# USB_Type-C_Port_V2_0.net
KiCad netlist of a schematic drawn in Altium Designer
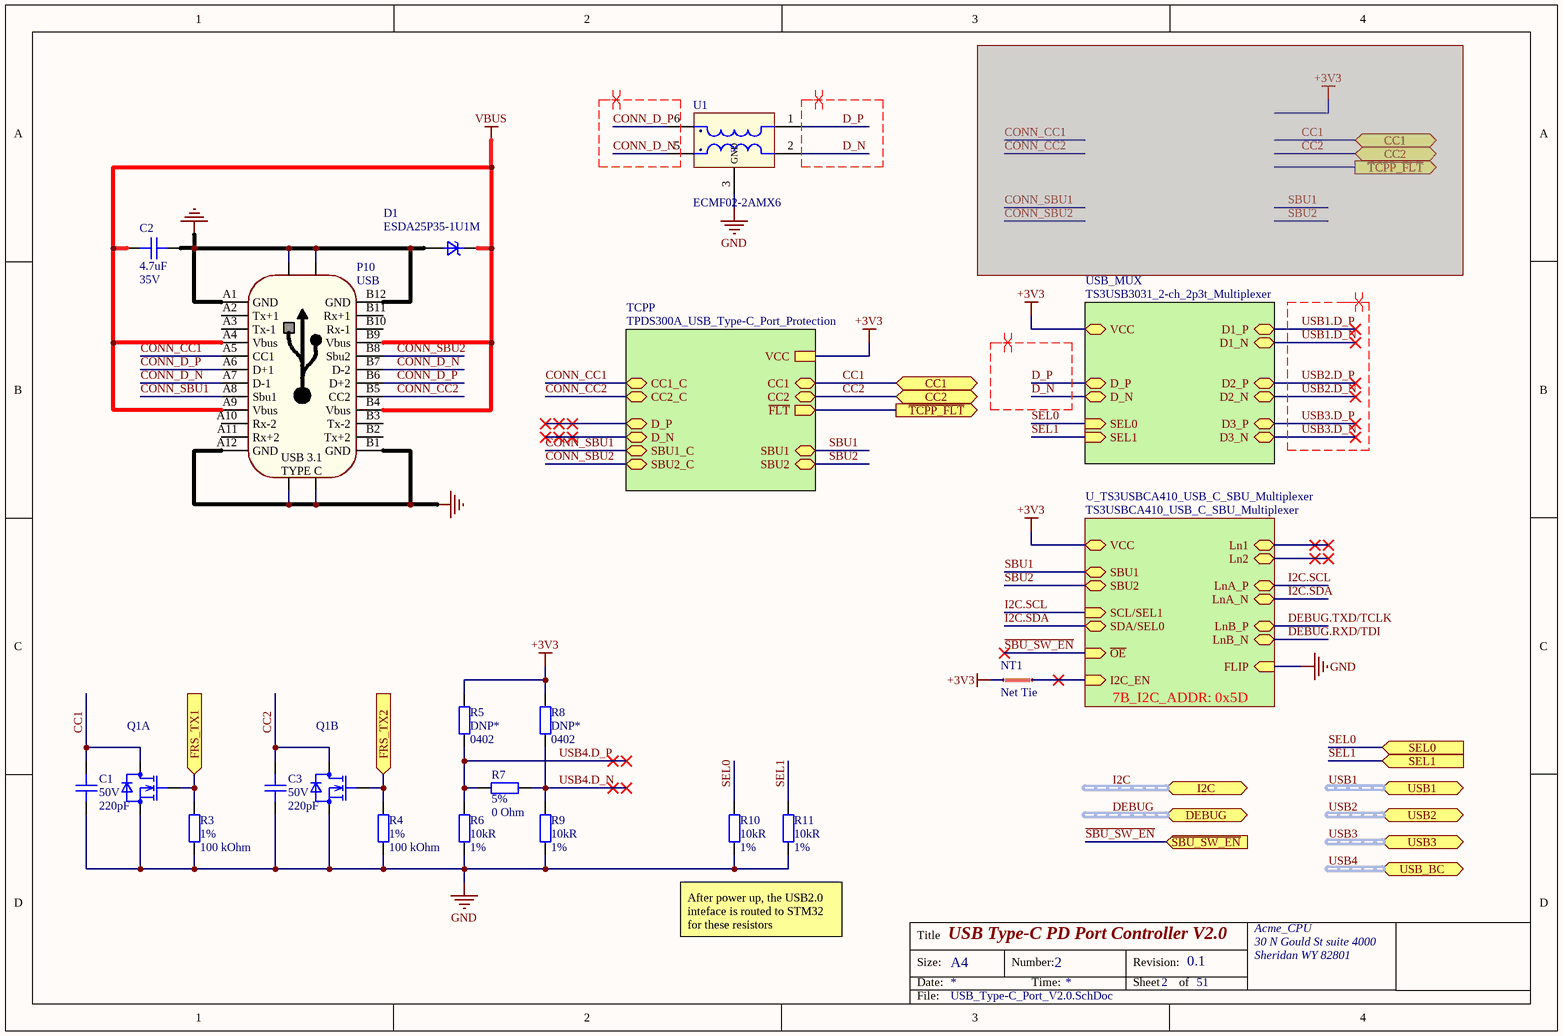
[diagram p0: USB_Type-C_Port_V2.0.SchDoc]

(export (version "E")
  (design (tool "Eeschema 10.0.6"))
  (components
    (comp (ref "C1")
      (value "CAP CER 220PF 50V X7R 0402")
      (footprint "C0402")
      (description "220pF ±10% 50V Ceramic Capacitor X7R 0402 (1005 Metric)")
      (fields
        (field (name "MANUFACTURER") "Yageo")
        (field (name "MANUFACTURER PART NUMBER") "CC0402KRX7R9BB221")
        (field (name "VOLTAGE RATING") "50V")
        (field (name "CAPACITANCE") "220pF")
      )
      (libsource (lib "capacitors_smd") (part "CAP CER 220PF 50V X7R 0402"))
    )
    (comp (ref "C2")
      (value "CAP CER 4.7UF 35V X7R 0805")
      (footprint "C0805")
      (fields
        (field (name "MANUFACTURER") "TDK")
        (field (name "MANUFACTURER PART NUMBER") "C2012X7R1V475K125AC")
        (field (name "TOLERANCE") "10%")
        (field (name "CAPACITANCE") "4.7uF")
        (field (name "VOLTAGE RATING") "35V")
      )
      (libsource (lib "capacitors_smd") (part "CAP CER 4.7UF 35V X7R 0805"))
    )
    (comp (ref "C3")
      (value "CAP CER 220PF 50V X7R 0402")
      (footprint "C0402")
      (description "220pF ±10% 50V Ceramic Capacitor X7R 0402 (1005 Metric)")
      (fields
        (field (name "MANUFACTURER") "Yageo")
        (field (name "MANUFACTURER PART NUMBER") "CC0402KRX7R9BB221")
        (field (name "VOLTAGE RATING") "50V")
        (field (name "CAPACITANCE") "220pF")
      )
      (libsource (lib "capacitors_smd") (part "CAP CER 220PF 50V X7R 0402"))
    )
    (comp (ref "D1")
      (value "ESDA25P35-1U1M")
      (footprint "ST_QFN_1610")
      (description "41V Clamp 35A (8/20µs) Ipp Tvs Diode Surface Mount 1610")
      (fields (field (name "MANUFACTURER") "STMicroelectronics"))
      (libsource (lib "diodes_tvs") (part "TVS DIODE ESDA25P35-1U1M 22V 41V 1610"))
    )
    (comp (ref "NT1")
      (value "Net Tie")
      (footprint "Net Tie 6x30mil")
      (libsource (lib "BLDC_Motor_Driver") (part "Net Tie Line"))
    )
    (comp (ref "P10")
      (value "USB")
      (footprint "MOLEX_2012670005")
      (fields (field (name "MANUFACTURER") "Molex") (field (name "MANUFACTURER PART NUMBER") "201267-0005"))
      (libsource (lib "connectors_usb") (part "CONN 2012670005 RCP USB3.1 TYPEC 24P SMD RA"))
    )
    (comp (ref "Q1")
      (value "DMN32D2LV-7")
      (footprint "SON_400UV-7_DIO")
      (description "Mosfet Array 2 N-Channel (Dual) 30V 400mA 400mW Surface Mount SOT-563")
      (fields (field (name "MANUFACTURER") "Diodes"))
      (libsource (lib "mosfets") (part "ARRAY MOSFET 2N-CH 30V 0.4A SOT-563"))
    )
    (comp (ref "R3")
      (value "RES SMD 100K OHM 1% 1/16W 0402")
      (footprint "R0402")
      (description "100 kOhms ±1% 0.063W, 1/16W Chip Resistor 0402 (1005 Metric) Moisture Resistant Thick Film")
      (fields
        (field (name "MANUFACTURER") "Yageo")
        (field (name "MANUFACTURER PART NUMBER") "RC0402FR-07100KL")
        (field (name "TOLERANCE") "1%")
        (field (name "RESISTANCE") "100 kOhm")
      )
      (libsource (lib "resistors_smd") (part "RES SMD 100K OHM 1% 1/16W 0402"))
    )
    (comp (ref "R4")
      (value "RES SMD 100K OHM 1% 1/16W 0402")
      (footprint "R0402")
      (description "100 kOhms ±1% 0.063W, 1/16W Chip Resistor 0402 (1005 Metric) Moisture Resistant Thick Film")
      (fields
        (field (name "MANUFACTURER") "Yageo")
        (field (name "MANUFACTURER PART NUMBER") "RC0402FR-07100KL")
        (field (name "TOLERANCE") "1%")
        (field (name "RESISTANCE") "100 kOhm")
      )
      (libsource (lib "resistors_smd") (part "RES SMD 100K OHM 1% 1/16W 0402"))
    )
    (comp (ref "R5")
      (value "DNP*")
      (footprint "R0402")
      (description "Placeholder for a 0402 resistor")
      (fields (field (name "CASE/PACKAGE") "0402"))
      (libsource (lib "resistors_smd") (part "RES SMD NO BOM 0402"))
    )
    (comp (ref "R6")
      (value "RES SMD 10K OHM 1% 1/16W 0402")
      (footprint "R0402")
      (description "10 kOhms ±1% 0.063W, 1/16W Chip Resistor 0402 (1005 Metric) Moisture Resistant Thick Film")
      (fields
        (field (name "MANUFACTURER") "Yageo")
        (field (name "MANUFACTURER PART NUMBER") "RC0402FR-0710KP")
        (field (name "RESISTANCE") "10kR")
        (field (name "TOLERANCE") "1%")
      )
      (libsource (lib "resistors_smd") (part "RES SMD 10K OHM 1% 1/16W 0402"))
    )
    (comp (ref "R7")
      (value "RES SMD 0 OHM JUMPER 1/16W 0402")
      (footprint "R0402")
      (description "0 Ohms Jumper 0.063W, 1/16W Chip Resistor 0402 (1005 Metric) Moisture Resistant Thick Film")
      (fields
        (field (name "MANUFACTURER") "Yageo")
        (field (name "MANUFACTURER PART NUMBER") "RC0402JR-070RL")
        (field (name "TOLERANCE") "5%")
        (field (name "RESISTANCE") "0 Ohm")
      )
      (libsource (lib "resistors_smd") (part "RES SMD 0 OHM JUMPER 1/16W 0402"))
    )
    (comp (ref "R8")
      (value "DNP*")
      (footprint "R0402")
      (description "Placeholder for a 0402 resistor")
      (fields (field (name "CASE/PACKAGE") "0402"))
      (libsource (lib "resistors_smd") (part "RES SMD NO BOM 0402"))
    )
    (comp (ref "R9")
      (value "RES SMD 10K OHM 1% 1/16W 0402")
      (footprint "R0402")
      (description "10 kOhms ±1% 0.063W, 1/16W Chip Resistor 0402 (1005 Metric) Moisture Resistant Thick Film")
      (fields
        (field (name "MANUFACTURER") "Yageo")
        (field (name "MANUFACTURER PART NUMBER") "RC0402FR-0710KP")
        (field (name "RESISTANCE") "10kR")
        (field (name "TOLERANCE") "1%")
      )
      (libsource (lib "resistors_smd") (part "RES SMD 10K OHM 1% 1/16W 0402"))
    )
    (comp (ref "R10")
      (value "RES SMD 10K OHM 1% 1/16W 0402")
      (footprint "R0402")
      (description "10 kOhms ±1% 0.063W, 1/16W Chip Resistor 0402 (1005 Metric) Moisture Resistant Thick Film")
      (fields
        (field (name "MANUFACTURER") "Yageo")
        (field (name "MANUFACTURER PART NUMBER") "RC0402FR-0710KP")
        (field (name "RESISTANCE") "10kR")
        (field (name "TOLERANCE") "1%")
      )
      (libsource (lib "resistors_smd") (part "RES SMD 10K OHM 1% 1/16W 0402"))
    )
    (comp (ref "R11")
      (value "RES SMD 10K OHM 1% 1/16W 0402")
      (footprint "R0402")
      (description "10 kOhms ±1% 0.063W, 1/16W Chip Resistor 0402 (1005 Metric) Moisture Resistant Thick Film")
      (fields
        (field (name "MANUFACTURER") "Yageo")
        (field (name "MANUFACTURER PART NUMBER") "RC0402FR-0710KP")
        (field (name "RESISTANCE") "10kR")
        (field (name "TOLERANCE") "1%")
      )
      (libsource (lib "resistors_smd") (part "RES SMD 10K OHM 1% 1/16W 0402"))
    )
    (comp (ref "U1")
      (value "ECMF02-2AMX6")
      (footprint "QFN-6L")
      (description "2 Line Common Mode Choke Surface Mount  200mA DCR 2.5Ohm")
      (fields (field (name "MANUFACTURER") "STMicroelectronics"))
      (libsource (lib "diodes_tvs") (part "CMC 200MA 2LN SMD ESD"))
    )
  )
  (nets
    (net (code "7") (name "+3V3") (class "Default")
      (node (ref "NT1") (pin "1") (pintype "passive"))
      (node (ref "R5") (pin "1") (pinfunction "1_1") (pintype "passive"))
      (node (ref "R8") (pin "1") (pinfunction "1_1") (pintype "passive"))
    )
    (net (code "8") (name "/CC1") (class "Default")
      (node (ref "C1") (pin "2") (pinfunction "2_2") (pintype "passive"))
      (node (ref "Q1") (pin "6") (pinfunction "D_6") (pintype "passive"))
    )
    (net (code "9") (name "/CC2") (class "Default")
      (node (ref "C3") (pin "2") (pinfunction "2_2") (pintype "passive"))
      (node (ref "Q1") (pin "3") (pinfunction "D_3") (pintype "passive"))
    )
    (net (code "10") (name "/CONN_CC1") (class "Default")
      (node (ref "P10") (pin "A5") (pinfunction "CC1_A5") (pintype "passive"))
    )
    (net (code "11") (name "/CONN_CC2") (class "Default")
      (node (ref "P10") (pin "B5") (pinfunction "CC2_B5") (pintype "passive"))
    )
    (net (code "12") (name "/CONN_D_N") (class "Default")
      (node (ref "P10") (pin "A7") (pinfunction "D-1_A7") (pintype "passive"))
      (node (ref "P10") (pin "B7") (pinfunction "D-2_B7") (pintype "passive"))
      (node (ref "U1") (pin "5") (pinfunction "OUT2_5") (pintype "passive"))
    )
    (net (code "13") (name "/CONN_D_P") (class "Default")
      (node (ref "P10") (pin "A6") (pinfunction "D+1_A6") (pintype "passive"))
      (node (ref "P10") (pin "B6") (pinfunction "D+2_B6") (pintype "passive"))
      (node (ref "U1") (pin "6") (pinfunction "OUT1_6") (pintype "passive"))
    )
    (net (code "14") (name "/CONN_SBU1") (class "Default")
      (node (ref "P10") (pin "A8") (pinfunction "Sbu1_A8") (pintype "passive"))
    )
    (net (code "15") (name "/CONN_SBU2") (class "Default")
      (node (ref "P10") (pin "B8") (pinfunction "Sbu2_B8") (pintype "passive"))
    )
    (net (code "18") (name "/D_N") (class "Default")
      (node (ref "U1") (pin "2") (pinfunction "INP2_2") (pintype "passive"))
    )
    (net (code "20") (name "/D_P") (class "Default")
      (node (ref "U1") (pin "1") (pinfunction "INP1_1") (pintype "passive"))
    )
    (net (code "22") (name "/FRS_TX1") (class "Default")
      (node (ref "Q1") (pin "2") (pinfunction "G_2") (pintype "passive"))
      (node (ref "R3") (pin "2") (pinfunction "2_2") (pintype "passive"))
    )
    (net (code "23") (name "/FRS_TX2") (class "Default")
      (node (ref "Q1") (pin "5") (pinfunction "G_5") (pintype "passive"))
      (node (ref "R4") (pin "2") (pinfunction "2_2") (pintype "passive"))
    )
    (net (code "26") (name "/I2C_EN") (class "Default") (node (ref "NT1") (pin "2") (pintype "passive")))
    (net (code "32") (name "/SEL0") (class "Default")
      (node (ref "R10") (pin "1") (pinfunction "1_1") (pintype "passive"))
    )
    (net (code "33") (name "/SEL1") (class "Default")
      (node (ref "R11") (pin "1") (pinfunction "1_1") (pintype "passive"))
    )
    (net (code "41") (name "/USB4.D_N") (class "Default")
      (node (ref "R7") (pin "2") (pinfunction "2_2") (pintype "passive"))
      (node (ref "R8") (pin "2") (pinfunction "2_2") (pintype "passive"))
      (node (ref "R9") (pin "1") (pinfunction "1_1") (pintype "passive"))
    )
    (net (code "42") (name "/USB4.D_P") (class "Default")
      (node (ref "R5") (pin "2") (pinfunction "2_2") (pintype "passive"))
      (node (ref "R6") (pin "1") (pinfunction "1_1") (pintype "passive"))
      (node (ref "R7") (pin "1") (pinfunction "1_1") (pintype "passive"))
    )
    (net (code "49") (name "GND") (class "Default")
      (node (ref "C1") (pin "1") (pinfunction "1_1") (pintype "passive"))
      (node (ref "C2") (pin "2") (pinfunction "2_2") (pintype "passive"))
      (node (ref "C3") (pin "1") (pinfunction "1_1") (pintype "passive"))
      (node (ref "D1") (pin "2") (pinfunction "A_2") (pintype "passive"))
      (node (ref "P10") (pin "A1") (pinfunction "GND_A1") (pintype "passive"))
      (node (ref "P10") (pin "A12") (pinfunction "GND_A12") (pintype "passive"))
      (node (ref "P10") (pin "B1") (pinfunction "GND_B1") (pintype "passive"))
      (node (ref "P10") (pin "B12") (pinfunction "GND_B12") (pintype "passive"))
      (node (ref "P10") (pin "S1") (pinfunction "S1_S1") (pintype "passive"))
      (node (ref "P10") (pin "S2") (pinfunction "S2_S2") (pintype "passive"))
      (node (ref "P10") (pin "S3") (pinfunction "S3_S3") (pintype "passive"))
      (node (ref "P10") (pin "S4") (pinfunction "S4_S4") (pintype "passive"))
      (node (ref "Q1") (pin "1") (pinfunction "S_1") (pintype "passive"))
      (node (ref "Q1") (pin "4") (pinfunction "S_4") (pintype "passive"))
      (node (ref "R10") (pin "2") (pinfunction "2_2") (pintype "passive"))
      (node (ref "R11") (pin "2") (pinfunction "2_2") (pintype "passive"))
      (node (ref "R3") (pin "1") (pinfunction "1_1") (pintype "passive"))
      (node (ref "R4") (pin "1") (pinfunction "1_1") (pintype "passive"))
      (node (ref "R6") (pin "2") (pinfunction "2_2") (pintype "passive"))
      (node (ref "R9") (pin "2") (pinfunction "2_2") (pintype "passive"))
      (node (ref "U1") (pin "3") (pinfunction "GND_3") (pintype "power_in"))
    )
    (net (code "50") (name "VBUS") (class "Default")
      (node (ref "C2") (pin "1") (pinfunction "1_1") (pintype "passive"))
      (node (ref "D1") (pin "1") (pinfunction "K_1") (pintype "passive"))
      (node (ref "P10") (pin "A4") (pinfunction "Vbus_A4") (pintype "passive"))
      (node (ref "P10") (pin "A9") (pinfunction "Vbus_A9") (pintype "passive"))
      (node (ref "P10") (pin "B4") (pinfunction "Vbus_B4") (pintype "passive"))
      (node (ref "P10") (pin "B9") (pinfunction "Vbus_B9") (pintype "passive"))
    )
    (net (code "51") (name "unconnected-(P10-Rx+1-PadB11)") (class "Default")
      (node (ref "P10") (pin "B11") (pinfunction "Rx+1_B11") (pintype "passive"))
    )
    (net (code "52") (name "unconnected-(P10-Rx+2-PadA11)") (class "Default")
      (node (ref "P10") (pin "A11") (pinfunction "Rx+2_A11") (pintype "passive"))
    )
    (net (code "53") (name "unconnected-(P10-Rx-1-PadB10)") (class "Default")
      (node (ref "P10") (pin "B10") (pinfunction "Rx-1_B10") (pintype "passive"))
    )
    (net (code "54") (name "unconnected-(P10-Rx-2-PadA10)") (class "Default")
      (node (ref "P10") (pin "A10") (pinfunction "Rx-2_A10") (pintype "passive"))
    )
    (net (code "55") (name "unconnected-(P10-Tx+1-PadA2)") (class "Default")
      (node (ref "P10") (pin "A2") (pinfunction "Tx+1_A2") (pintype "passive"))
    )
    (net (code "56") (name "unconnected-(P10-Tx+2-PadB2)") (class "Default")
      (node (ref "P10") (pin "B2") (pinfunction "Tx+2_B2") (pintype "passive"))
    )
    (net (code "57") (name "unconnected-(P10-Tx-1-PadA3)") (class "Default")
      (node (ref "P10") (pin "A3") (pinfunction "Tx-1_A3") (pintype "passive"))
    )
    (net (code "58") (name "unconnected-(P10-Tx-2-PadB3)") (class "Default")
      (node (ref "P10") (pin "B3") (pinfunction "Tx-2_B3") (pintype "passive"))
    )
    (net (code "59") (name "unconnected-(U1-NC-Pad4)") (class "Default")
      (node (ref "U1") (pin "4") (pinfunction "NC_4") (pintype "passive"))
    )
  )
)
